# hackerling.net
KiCad netlist of a schematic drawn in EAGLE
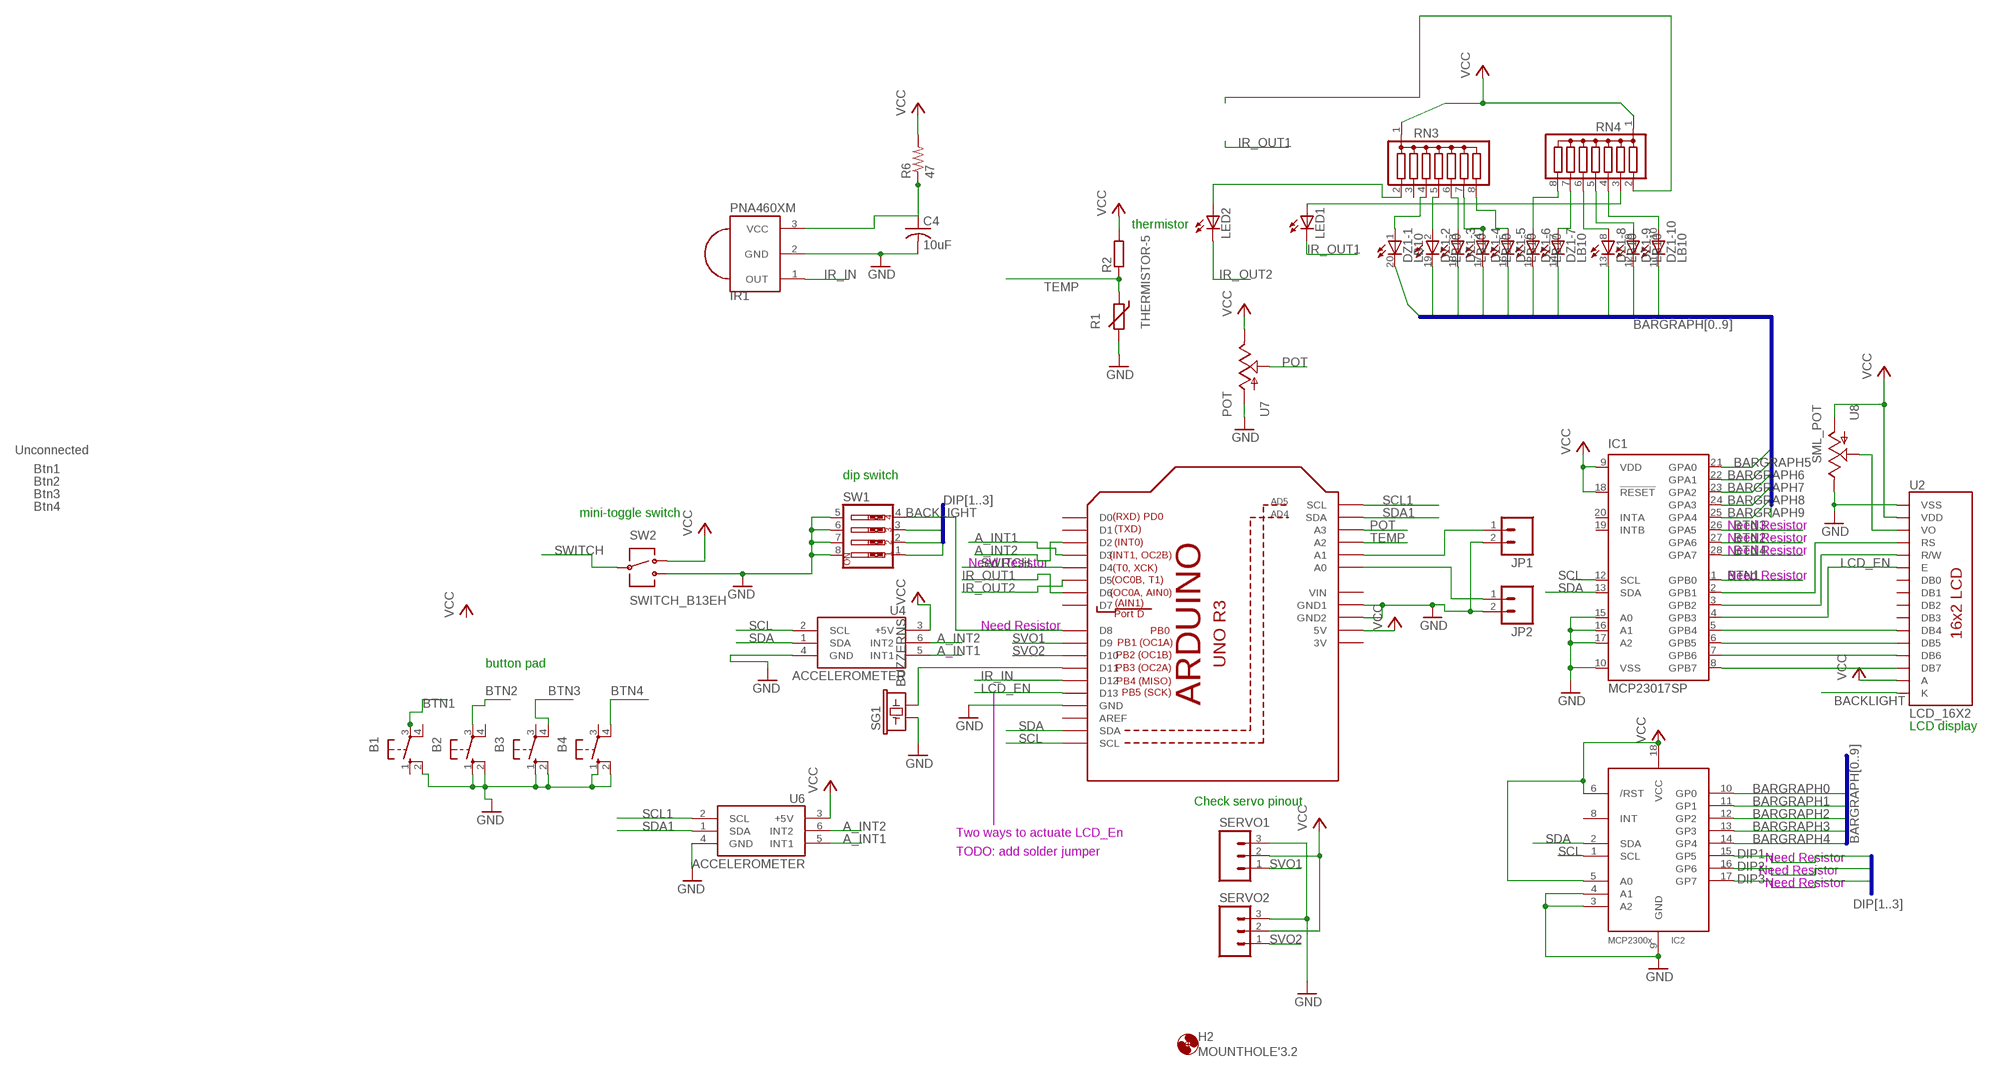
[diagram p0: schematic, sheet 1, part 1 of 2]
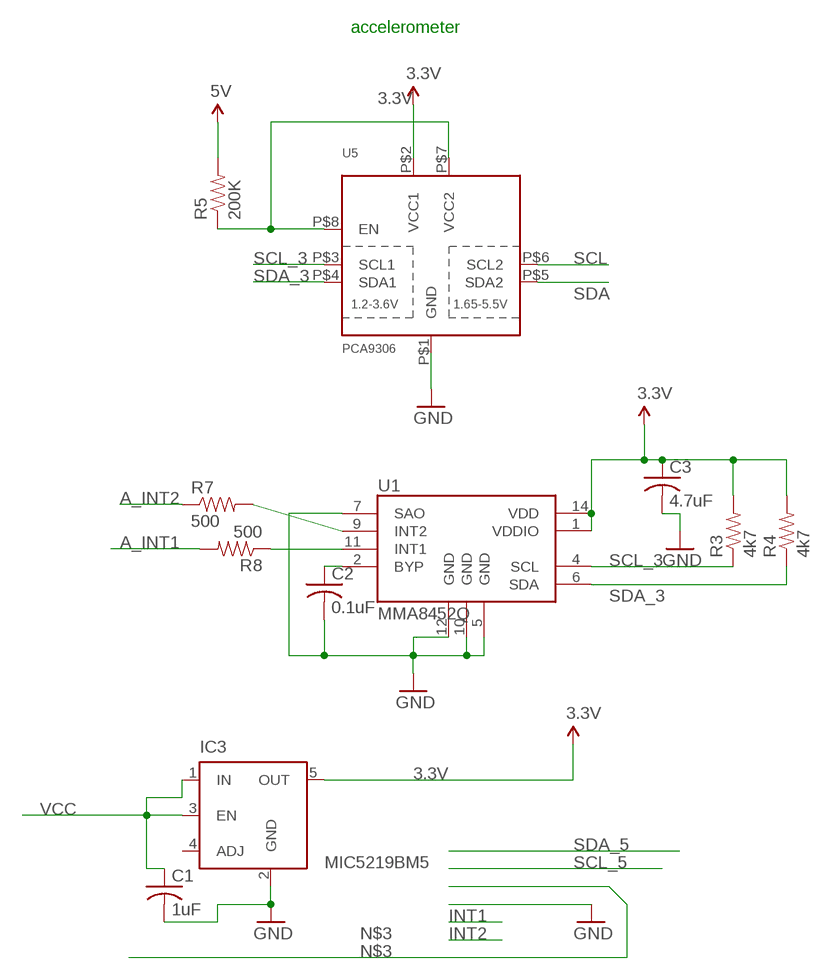
[diagram p1: schematic, sheet 1, part 2 of 2]

(export (version "E")
  (design (tool "Eeschema 10.0.6"))
  (components
    (comp (ref "B1")
      (value "SWITCH_BCF-4000")
      (footprint "eagle-import:SWITCH_B3F-4000")
      (libsource (lib "eagle-import") (part "SWITCH_BCF-4000"))
    )
    (comp (ref "B2")
      (value "SWITCH_BCF-4000")
      (footprint "eagle-import:SWITCH_B3F-4000")
      (libsource (lib "eagle-import") (part "SWITCH_BCF-4000"))
    )
    (comp (ref "B3")
      (value "SWITCH_BCF-4000")
      (footprint "eagle-import:SWITCH_B3F-4000")
      (libsource (lib "eagle-import") (part "SWITCH_BCF-4000"))
    )
    (comp (ref "B4")
      (value "SWITCH_BCF-4000")
      (footprint "eagle-import:SWITCH_B3F-4000")
      (libsource (lib "eagle-import") (part "SWITCH_BCF-4000"))
    )
    (comp (ref "C1")
      (value "1uF")
      (footprint "eagle-import:C0603K")
      (libsource (lib "eagle-import") (part "resistor_C-USC0603K"))
    )
    (comp (ref "C2")
      (value "0.1uF")
      (footprint "eagle-import:C0603K")
      (libsource (lib "eagle-import") (part "resistor_C-USC0603K"))
    )
    (comp (ref "C3")
      (value "4.7uF")
      (footprint "eagle-import:C0603K")
      (libsource (lib "eagle-import") (part "resistor_C-USC0603K"))
    )
    (comp (ref "C4")
      (value "10uF")
      (footprint "eagle-import:C050-050X075")
      (libsource (lib "eagle-import") (part "C-US050-050X075"))
    )
    (comp (ref "DZ1")
      (value "LB10")
      (footprint "eagle-import:LB10")
      (libsource (lib "eagle-import") (part "LB10"))
    )
    (comp (ref "H2")
      (value "MOUNTHOLE'3.2")
      (footprint "eagle-import:HOLE_3.2")
      (libsource (lib "eagle-import") (part "MOUNTHOLE'3.2"))
    )
    (comp (ref "IC1")
      (value "MCP23017SP")
      (footprint "eagle-import:DIL28-3")
      (libsource (lib "eagle-import") (part "MCP23017SP"))
    )
    (comp (ref "IC2")
      (value "MCP2300X/P")
      (footprint "eagle-import:DIL18")
      (libsource (lib "eagle-import") (part "MCP2300X/P"))
    )
    (comp (ref "IC3")
      (value "MIC5219BM5")
      (footprint "eagle-import:SOT23-5")
      (fields (field (name "MF") "ALTERA CORPORATION") (field (name "MPN") "MIC5219BM5 TR"))
      (libsource (lib "eagle-import") (part "MIC5219BM5"))
    )
    (comp (ref "IR1")
      (value "PNA460XM")
      (footprint "eagle-import:PNA460XM")
      (libsource (lib "eagle-import") (part "PNA460XM"))
    )
    (comp (ref "JP1")
      (value "M02LOCK")
      (footprint "eagle-import:1X02_LOCK")
      (libsource (lib "eagle-import") (part "M02LOCK"))
    )
    (comp (ref "JP2")
      (value "M02LOCK")
      (footprint "eagle-import:1X02_LOCK")
      (libsource (lib "eagle-import") (part "M02LOCK"))
    )
    (comp (ref "LED1")
      (value "LED5MM")
      (footprint "eagle-import:LED5MM")
      (libsource (lib "eagle-import") (part "LED5MM"))
    )
    (comp (ref "LED2")
      (value "LED5MM")
      (footprint "eagle-import:LED5MM")
      (libsource (lib "eagle-import") (part "LED5MM"))
    )
    (comp (ref "R1")
      (value "THERMISTOR-5")
      (footprint "eagle-import:R-5")
      (libsource (lib "eagle-import") (part "THERMISTOR-5"))
    )
    (comp (ref "R2")
      (value "R-EU_0204/7")
      (footprint "eagle-import:0204_7")
      (libsource (lib "eagle-import") (part "R-EU_0204/7"))
    )
    (comp (ref "R3")
      (value "4k7")
      (footprint "eagle-import:0603-RES")
      (libsource (lib "eagle-import") (part "RESISTOR0603-RES"))
    )
    (comp (ref "R4")
      (value "4k7")
      (footprint "eagle-import:0603-RES")
      (libsource (lib "eagle-import") (part "RESISTOR0603-RES"))
    )
    (comp (ref "R5")
      (value "200K")
      (footprint "eagle-import:0603-RES")
      (libsource (lib "eagle-import") (part "RESISTOR0603-RES"))
    )
    (comp (ref "R6")
      (value "47")
      (footprint "eagle-import:0204_7")
      (libsource (lib "eagle-import") (part "R-US_0204/7"))
    )
    (comp (ref "R7")
      (value "500")
      (footprint "eagle-import:0603-RES")
      (libsource (lib "eagle-import") (part "RESISTOR0603-RES"))
    )
    (comp (ref "R8")
      (value "500")
      (footprint "eagle-import:0603-RES")
      (libsource (lib "eagle-import") (part "RESISTOR0603-RES"))
    )
    (comp (ref "RN3")
      (value "G07R")
      (footprint "eagle-import:SIL8")
      (libsource (lib "eagle-import") (part "G07R"))
    )
    (comp (ref "RN4")
      (value "G07R")
      (footprint "eagle-import:SIL8")
      (libsource (lib "eagle-import") (part "G07R"))
    )
    (comp (ref "SERVO1")
      (value "M03LOCK")
      (footprint "eagle-import:1X03_LOCK")
      (libsource (lib "eagle-import") (part "M03LOCK"))
    )
    (comp (ref "SERVO2")
      (value "M03LOCK")
      (footprint "eagle-import:1X03_LOCK")
      (libsource (lib "eagle-import") (part "M03LOCK"))
    )
    (comp (ref "SG1")
      (value "BUZZERNS")
      (footprint "eagle-import:BUZZER-12MM-NS")
      (libsource (lib "eagle-import") (part "BUZZERNS"))
    )
    (comp (ref "SW1")
      (value "SW_DIP-4")
      (footprint "eagle-import:EDG-04")
      (libsource (lib "eagle-import") (part "SW_DIP-4"))
    )
    (comp (ref "SW2")
      (value "SWITCH_B13EH")
      (footprint "eagle-import:SWITCH_B13EH")
      (libsource (lib "eagle-import") (part "SWITCH_B13EH"))
    )
    (comp (ref "U1")
      (value "MMA8452Q")
      (footprint "eagle-import:QFN-16(5X3)")
      (libsource (lib "eagle-import") (part "MMA8452Q"))
    )
    (comp (ref "U2")
      (value "LCD_16X2")
      (footprint "eagle-import:LCD_16X2")
      (libsource (lib "eagle-import") (part "LCD_16X2"))
    )
    (comp (ref "U3")
      (value "ARDUINOR3-BPLACE")
      (footprint "eagle-import:ARDUINOR3-BPLACE")
      (libsource (lib "eagle-import") (part "ARDUINOR3-BPLACE"))
    )
    (comp (ref "U4")
      (value "ACCELEROMETER")
      (footprint "eagle-import:ACCELEROMETER")
      (libsource (lib "eagle-import") (part "ACCELEROMETER"))
    )
    (comp (ref "U5")
      (value "PCA9306")
      (footprint "eagle-import:VSSOP-8")
      (libsource (lib "eagle-import") (part "PCA9306"))
    )
    (comp (ref "U6")
      (value "ACCELEROMETER")
      (footprint "eagle-import:ACCELEROMETER")
      (libsource (lib "eagle-import") (part "ACCELEROMETER"))
    )
    (comp (ref "U7")
      (value "POT")
      (footprint "eagle-import:ALS_POT")
      (libsource (lib "eagle-import") (part "POT"))
    )
    (comp (ref "U8")
      (value "SML_POT")
      (footprint "eagle-import:SML_POT")
      (libsource (lib "eagle-import") (part "SML_POT"))
    )
  )
  (nets
    (net (code "1") (name "/3V") (class "Default")
      (node (ref "U3") (pin "3V") (pinfunction "3V_3V") (pintype "power_in"))
    )
    (net (code "2") (name "/A_INT1") (class "Default")
      (node (ref "R8") (pin "2") (pinfunction "2_2") (pintype "passive"))
      (node (ref "U3") (pin "D3") (pinfunction "D3_D3") (pintype "bidirectional"))
      (node (ref "U4") (pin "5") (pinfunction "INT1_5") (pintype "bidirectional"))
      (node (ref "U6") (pin "5") (pinfunction "INT1_5") (pintype "bidirectional"))
    )
    (net (code "3") (name "/A_INT2") (class "Default")
      (node (ref "R7") (pin "1") (pinfunction "1_1") (pintype "passive"))
      (node (ref "U3") (pin "D2") (pinfunction "D2_D2") (pintype "bidirectional"))
      (node (ref "U4") (pin "6") (pinfunction "INT2_6") (pintype "bidirectional"))
      (node (ref "U6") (pin "6") (pinfunction "INT2_6") (pintype "bidirectional"))
    )
    (net (code "4") (name "/BACKLIGHT") (class "Default")
      (node (ref "SW1") (pin "4") (pinfunction "4_4") (pintype "passive"))
      (node (ref "U2") (pin "16") (pinfunction "K_16") (pintype "power_in"))
      (node (ref "U3") (pin "D8") (pinfunction "D8_D8") (pintype "bidirectional"))
    )
    (net (code "5") (name "/BARGRAPH0") (class "Default")
      (node (ref "DZ1") (pin "20") (pinfunction "C_20") (pintype "passive"))
      (node (ref "IC2") (pin "10") (pinfunction "GP0_10") (pintype "bidirectional"))
    )
    (net (code "6") (name "/BARGRAPH1") (class "Default")
      (node (ref "DZ1") (pin "19") (pinfunction "C_19") (pintype "passive"))
      (node (ref "IC2") (pin "11") (pinfunction "GP1_11") (pintype "bidirectional"))
    )
    (net (code "7") (name "/BARGRAPH2") (class "Default")
      (node (ref "DZ1") (pin "18") (pinfunction "C_18") (pintype "passive"))
      (node (ref "IC2") (pin "12") (pinfunction "GP2_12") (pintype "bidirectional"))
    )
    (net (code "8") (name "/BARGRAPH3") (class "Default")
      (node (ref "DZ1") (pin "17") (pinfunction "C_17") (pintype "passive"))
      (node (ref "IC2") (pin "13") (pinfunction "GP3_13") (pintype "bidirectional"))
    )
    (net (code "9") (name "/BARGRAPH4") (class "Default")
      (node (ref "DZ1") (pin "16") (pinfunction "C_16") (pintype "passive"))
      (node (ref "IC2") (pin "14") (pinfunction "GP4_14") (pintype "bidirectional"))
    )
    (net (code "10") (name "/BARGRAPH5") (class "Default")
      (node (ref "DZ1") (pin "15") (pinfunction "C_15") (pintype "passive"))
      (node (ref "IC1") (pin "21") (pinfunction "GPA0_21") (pintype "bidirectional"))
    )
    (net (code "11") (name "/BARGRAPH6") (class "Default")
      (node (ref "DZ1") (pin "14") (pinfunction "C_14") (pintype "passive"))
      (node (ref "IC1") (pin "22") (pinfunction "GPA1_22") (pintype "bidirectional"))
    )
    (net (code "12") (name "/BARGRAPH7") (class "Default")
      (node (ref "DZ1") (pin "13") (pinfunction "C_13") (pintype "passive"))
      (node (ref "IC1") (pin "23") (pinfunction "GPA2_23") (pintype "bidirectional"))
    )
    (net (code "13") (name "/BARGRAPH8") (class "Default")
      (node (ref "DZ1") (pin "12") (pinfunction "C_12") (pintype "passive"))
      (node (ref "IC1") (pin "24") (pinfunction "GPA3_24") (pintype "bidirectional"))
    )
    (net (code "14") (name "/BARGRAPH9") (class "Default")
      (node (ref "DZ1") (pin "11") (pinfunction "C_11") (pintype "passive"))
      (node (ref "IC1") (pin "25") (pinfunction "GPA4_25") (pintype "bidirectional"))
    )
    (net (code "16") (name "/BTN1") (class "Default")
      (node (ref "B1") (pin "3") (pinfunction "P_3") (pintype "passive"))
      (node (ref "IC1") (pin "1") (pinfunction "GPB0_1") (pintype "bidirectional"))
    )
    (net (code "17") (name "/BTN2") (class "Default")
      (node (ref "B2") (pin "3") (pinfunction "P_3") (pintype "passive"))
      (node (ref "IC1") (pin "27") (pinfunction "GPA6_27") (pintype "bidirectional"))
    )
    (net (code "18") (name "/BTN3") (class "Default")
      (node (ref "B3") (pin "4") (pinfunction "P1_4") (pintype "passive"))
      (node (ref "IC1") (pin "26") (pinfunction "GPA5_26") (pintype "bidirectional"))
    )
    (net (code "19") (name "/BTN4") (class "Default")
      (node (ref "B4") (pin "4") (pinfunction "P1_4") (pintype "passive"))
      (node (ref "IC1") (pin "28") (pinfunction "GPA7_28") (pintype "bidirectional"))
    )
    (net (code "20") (name "/DIP1") (class "Default")
      (node (ref "IC2") (pin "15") (pinfunction "GP5_15") (pintype "bidirectional"))
      (node (ref "SW1") (pin "1") (pinfunction "1_1") (pintype "passive"))
    )
    (net (code "21") (name "/DIP2") (class "Default")
      (node (ref "IC2") (pin "16") (pinfunction "GP6_16") (pintype "bidirectional"))
      (node (ref "SW1") (pin "2") (pinfunction "2_2") (pintype "passive"))
    )
    (net (code "22") (name "/DIP3") (class "Default")
      (node (ref "IC2") (pin "17") (pinfunction "GP7_17") (pintype "bidirectional"))
      (node (ref "SW1") (pin "3") (pinfunction "3_3") (pintype "passive"))
    )
    (net (code "26") (name "/IR_IN") (class "Default")
      (node (ref "IR1") (pin "1") (pinfunction "OUT_1") (pintype "output"))
      (node (ref "U3") (pin "D12") (pinfunction "D12_D12") (pintype "bidirectional"))
    )
    (net (code "27") (name "/IR_OUT1") (class "Default")
      (node (ref "LED1") (pin "K") (pinfunction "C_K") (pintype "passive"))
      (node (ref "U3") (pin "D6") (pinfunction "D6_D6") (pintype "bidirectional"))
    )
    (net (code "28") (name "/IR_OUT2") (class "Default")
      (node (ref "LED2") (pin "K") (pinfunction "C_K") (pintype "passive"))
      (node (ref "U3") (pin "D5") (pinfunction "D5_D5") (pintype "bidirectional"))
    )
    (net (code "29") (name "/LCD_EN") (class "Default")
      (node (ref "IC1") (pin "4") (pinfunction "GPB3_4") (pintype "bidirectional"))
      (node (ref "U2") (pin "6") (pinfunction "E_6") (pintype "input"))
      (node (ref "U3") (pin "D13") (pinfunction "D13_D13") (pintype "bidirectional"))
    )
    (net (code "30") (name "/N$3") (class "Default")
      (node (ref "IC1") (pin "6") (pinfunction "GPB5_6") (pintype "bidirectional"))
      (node (ref "U2") (pin "12") (pinfunction "DB5_12") (pintype "bidirectional"))
      (node (ref "U2") (pin "B12") (pinfunction "DB5_B12") (pintype "bidirectional"))
    )
    (net (code "31") (name "/POT") (class "Default")
      (node (ref "U3") (pin "A3") (pinfunction "A3_A3") (pintype "bidirectional"))
      (node (ref "U7") (pin "P$2") (pinfunction "S_P$2") (pintype "passive"))
    )
    (net (code "32") (name "/SCL") (class "Default")
      (node (ref "IC1") (pin "12") (pinfunction "SCL_12") (pintype "input"))
      (node (ref "IC2") (pin "1") (pinfunction "SCL_1") (pintype "bidirectional"))
      (node (ref "U3") (pin "SCL") (pinfunction "SCL_SCL") (pintype "bidirectional"))
      (node (ref "U4") (pin "2") (pinfunction "SCL_2") (pintype "bidirectional"))
      (node (ref "U5") (pin "P$6") (pinfunction "SCL2_P$6") (pintype "bidirectional"))
    )
    (net (code "33") (name "/SCL1") (class "Default")
      (node (ref "U3") (pin "A5") (pinfunction "SCL_A5") (pintype "bidirectional"))
      (node (ref "U6") (pin "2") (pinfunction "SCL_2") (pintype "bidirectional"))
    )
    (net (code "34") (name "/SCL_3") (class "Default")
      (node (ref "R3") (pin "1") (pinfunction "1_1") (pintype "passive"))
      (node (ref "U1") (pin "4") (pinfunction "SCL_4") (pintype "bidirectional"))
      (node (ref "U5") (pin "P$3") (pinfunction "SCL1_P$3") (pintype "bidirectional"))
    )
    (net (code "36") (name "/SDA") (class "Default")
      (node (ref "IC1") (pin "13") (pinfunction "SDA_13") (pintype "bidirectional"))
      (node (ref "IC2") (pin "2") (pinfunction "SDA_2") (pintype "bidirectional"))
      (node (ref "U3") (pin "SDA") (pinfunction "SDA_SDA") (pintype "bidirectional"))
      (node (ref "U4") (pin "1") (pinfunction "SDA_1") (pintype "bidirectional"))
      (node (ref "U5") (pin "P$5") (pinfunction "SDA2_P$5") (pintype "bidirectional"))
    )
    (net (code "37") (name "/SDA1") (class "Default")
      (node (ref "U3") (pin "A4") (pinfunction "SDA_A4") (pintype "bidirectional"))
      (node (ref "U6") (pin "1") (pinfunction "SDA_1") (pintype "bidirectional"))
    )
    (net (code "38") (name "/SDA_3") (class "Default")
      (node (ref "R4") (pin "1") (pinfunction "1_1") (pintype "passive"))
      (node (ref "U1") (pin "6") (pinfunction "SDA_6") (pintype "bidirectional"))
      (node (ref "U5") (pin "P$4") (pinfunction "SDA1_P$4") (pintype "bidirectional"))
    )
    (net (code "40") (name "/SVO1") (class "Default")
      (node (ref "SERVO1") (pin "1") (pinfunction "1_1") (pintype "passive"))
      (node (ref "U3") (pin "D9") (pinfunction "D9_D9") (pintype "bidirectional"))
    )
    (net (code "41") (name "/SVO2") (class "Default")
      (node (ref "SERVO2") (pin "1") (pinfunction "1_1") (pintype "passive"))
      (node (ref "U3") (pin "D10") (pinfunction "D10_D10") (pintype "bidirectional"))
    )
    (net (code "42") (name "/SWITCH") (class "Default")
      (node (ref "SW2") (pin "2") (pinfunction "2_2") (pintype "bidirectional"))
      (node (ref "U3") (pin "D4") (pinfunction "D4_D4") (pintype "bidirectional"))
    )
    (net (code "43") (name "/TEMP") (class "Default")
      (node (ref "R1") (pin "1") (pinfunction "1_1") (pintype "passive"))
      (node (ref "R2") (pin "1") (pinfunction "1_1") (pintype "passive"))
      (node (ref "U3") (pin "A2") (pinfunction "A2_A2") (pintype "bidirectional"))
    )
    (net (code "44") (name "/VIN") (class "Default")
      (node (ref "U3") (pin "VIN") (pinfunction "VIN_VIN") (pintype "power_in"))
    )
    (net (code "45") (name "3.3V") (class "Default")
      (node (ref "C3") (pin "1") (pinfunction "1_1") (pintype "passive"))
      (node (ref "IC3") (pin "5") (pinfunction "OUT_5") (pintype "output"))
      (node (ref "R3") (pin "2") (pinfunction "2_2") (pintype "passive"))
      (node (ref "R4") (pin "2") (pinfunction "2_2") (pintype "passive"))
      (node (ref "U1") (pin "1") (pinfunction "VDDIO_1") (pintype "bidirectional"))
      (node (ref "U1") (pin "14") (pinfunction "VDD_14") (pintype "bidirectional"))
      (node (ref "U5") (pin "P$2") (pinfunction "VCC1_P$2") (pintype "bidirectional"))
    )
    (net (code "46") (name "5V") (class "Default")
      (node (ref "C1") (pin "1") (pinfunction "1_1") (pintype "passive"))
      (node (ref "IC1") (pin "18") (pinfunction "~{RESET}_18") (pintype "input"))
      (node (ref "IC1") (pin "9") (pinfunction "VDD_9") (pintype "power_in"))
      (node (ref "IC2") (pin "18") (pinfunction "VCC_18") (pintype "power_in"))
      (node (ref "IC2") (pin "5") (pinfunction "A0_5") (pintype "input"))
      (node (ref "IC2") (pin "6") (pinfunction "/RST_6") (pintype "input"))
      (node (ref "IC3") (pin "1") (pinfunction "IN_1") (pintype "input"))
      (node (ref "IC3") (pin "3") (pinfunction "EN_3") (pintype "input"))
      (node (ref "R2") (pin "2") (pinfunction "2_2") (pintype "passive"))
      (node (ref "R5") (pin "2") (pinfunction "2_2") (pintype "passive"))
      (node (ref "R6") (pin "2") (pinfunction "2_2") (pintype "passive"))
      (node (ref "RN3") (pin "1") (pinfunction "1_1") (pintype "passive"))
      (node (ref "RN4") (pin "1") (pinfunction "1_1") (pintype "passive"))
      (node (ref "SERVO1") (pin "2") (pinfunction "2_2") (pintype "passive"))
      (node (ref "SERVO2") (pin "2") (pinfunction "2_2") (pintype "passive"))
      (node (ref "SW2") (pin "1") (pinfunction "1_1") (pintype "bidirectional"))
      (node (ref "U2") (pin "15") (pinfunction "A_15") (pintype "power_in"))
      (node (ref "U2") (pin "2") (pinfunction "VDD_2") (pintype "power_in"))
      (node (ref "U2") (pin "B2") (pinfunction "VDD_B2") (pintype "power_in"))
      (node (ref "U3") (pin "5V") (pinfunction "5V_5V") (pintype "power_in"))
      (node (ref "U4") (pin "3") (pinfunction "+5V_3") (pintype "bidirectional"))
      (node (ref "U6") (pin "3") (pinfunction "+5V_3") (pintype "bidirectional"))
      (node (ref "U7") (pin "P$3") (pinfunction "E_P$3") (pintype "passive"))
      (node (ref "U8") (pin "A") (pinfunction "A_A") (pintype "passive"))
    )
    (net (code "47") (name "GND") (class "Default")
      (node (ref "B1") (pin "2") (pinfunction "S1_2") (pintype "passive"))
      (node (ref "B2") (pin "1") (pinfunction "S_1") (pintype "passive"))
      (node (ref "B2") (pin "2") (pinfunction "S1_2") (pintype "passive"))
      (node (ref "B3") (pin "1") (pinfunction "S_1") (pintype "passive"))
      (node (ref "B3") (pin "2") (pinfunction "S1_2") (pintype "passive"))
      (node (ref "B4") (pin "1") (pinfunction "S_1") (pintype "passive"))
      (node (ref "B4") (pin "2") (pinfunction "S1_2") (pintype "passive"))
      (node (ref "C1") (pin "2") (pinfunction "2_2") (pintype "passive"))
      (node (ref "C2") (pin "2") (pinfunction "2_2") (pintype "passive"))
      (node (ref "C3") (pin "2") (pinfunction "2_2") (pintype "passive"))
      (node (ref "C4") (pin "2") (pinfunction "2_2") (pintype "passive"))
      (node (ref "IC1") (pin "10") (pinfunction "VSS_10") (pintype "power_in"))
      (node (ref "IC1") (pin "15") (pinfunction "A0_15") (pintype "input"))
      (node (ref "IC1") (pin "16") (pinfunction "A1_16") (pintype "input"))
      (node (ref "IC1") (pin "17") (pinfunction "A2_17") (pintype "input"))
      (node (ref "IC2") (pin "3") (pinfunction "A2_3") (pintype "input"))
      (node (ref "IC2") (pin "4") (pinfunction "A1_4") (pintype "input"))
      (node (ref "IC2") (pin "9") (pinfunction "GND_9") (pintype "power_in"))
      (node (ref "IC3") (pin "2") (pinfunction "GND_2") (pintype "power_in"))
      (node (ref "IR1") (pin "2") (pinfunction "GND_2") (pintype "power_in"))
      (node (ref "JP1") (pin "2") (pinfunction "2_2") (pintype "passive"))
      (node (ref "JP2") (pin "2") (pinfunction "2_2") (pintype "passive"))
      (node (ref "R1") (pin "2") (pinfunction "2_2") (pintype "passive"))
      (node (ref "SERVO1") (pin "3") (pinfunction "3_3") (pintype "passive"))
      (node (ref "SERVO2") (pin "3") (pinfunction "3_3") (pintype "passive"))
      (node (ref "SG1") (pin "+") (pinfunction "1_+") (pintype "passive"))
      (node (ref "SW1") (pin "5") (pinfunction "5_5") (pintype "passive"))
      (node (ref "SW1") (pin "6") (pinfunction "6_6") (pintype "passive"))
      (node (ref "SW1") (pin "7") (pinfunction "7_7") (pintype "passive"))
      (node (ref "SW1") (pin "8") (pinfunction "8_8") (pintype "passive"))
      (node (ref "SW2") (pin "3") (pinfunction "3_3") (pintype "bidirectional"))
      (node (ref "U1") (pin "10") (pinfunction "GND_10") (pintype "bidirectional"))
      (node (ref "U1") (pin "12") (pinfunction "GND_12") (pintype "bidirectional"))
      (node (ref "U1") (pin "5") (pinfunction "GND_5") (pintype "bidirectional"))
      (node (ref "U1") (pin "7") (pinfunction "SAO_7") (pintype "bidirectional"))
      (node (ref "U2") (pin "1") (pinfunction "VSS_1") (pintype "power_in"))
      (node (ref "U2") (pin "B1") (pinfunction "VSS_B1") (pintype "power_in"))
      (node (ref "U3") (pin "GND") (pinfunction "GND_GND") (pintype "power_in"))
      (node (ref "U3") (pin "GND1") (pinfunction "GND1_GND1") (pintype "power_in"))
      (node (ref "U3") (pin "GND2") (pinfunction "GND2_GND2") (pintype "power_in"))
      (node (ref "U4") (pin "4") (pinfunction "GND_4") (pintype "bidirectional"))
      (node (ref "U5") (pin "P$1") (pinfunction "GND_P$1") (pintype "bidirectional"))
      (node (ref "U6") (pin "4") (pinfunction "GND_4") (pintype "bidirectional"))
      (node (ref "U7") (pin "P$1") (pinfunction "A_P$1") (pintype "passive"))
      (node (ref "U8") (pin "E") (pinfunction "E_E") (pintype "passive"))
    )
    (net (code "48") (name "Net-(DZ1A-A)") (class "Default")
      (node (ref "DZ1") (pin "1") (pinfunction "A_1") (pintype "passive"))
      (node (ref "RN3") (pin "4") (pinfunction "4_4") (pintype "passive"))
    )
    (net (code "49") (name "Net-(DZ1B-A)") (class "Default")
      (node (ref "DZ1") (pin "10") (pinfunction "A_10") (pintype "passive"))
      (node (ref "RN4") (pin "4") (pinfunction "4_4") (pintype "passive"))
    )
    (net (code "50") (name "Net-(DZ1C-A)") (class "Default")
      (node (ref "DZ1") (pin "2") (pinfunction "A_2") (pintype "passive"))
      (node (ref "RN3") (pin "5") (pinfunction "5_5") (pintype "passive"))
    )
    (net (code "51") (name "Net-(DZ1D-A)") (class "Default")
      (node (ref "DZ1") (pin "3") (pinfunction "A_3") (pintype "passive"))
      (node (ref "RN3") (pin "6") (pinfunction "6_6") (pintype "passive"))
    )
    (net (code "52") (name "Net-(DZ1E-A)") (class "Default")
      (node (ref "DZ1") (pin "4") (pinfunction "A_4") (pintype "passive"))
      (node (ref "RN3") (pin "7") (pinfunction "7_7") (pintype "passive"))
    )
    (net (code "53") (name "Net-(DZ1F-A)") (class "Default")
      (node (ref "DZ1") (pin "5") (pinfunction "A_5") (pintype "passive"))
      (node (ref "RN3") (pin "8") (pinfunction "8_8") (pintype "passive"))
    )
    (net (code "54") (name "Net-(DZ1G-A)") (class "Default")
      (node (ref "DZ1") (pin "6") (pinfunction "A_6") (pintype "passive"))
      (node (ref "RN4") (pin "8") (pinfunction "8_8") (pintype "passive"))
    )
    (net (code "55") (name "Net-(DZ1H-A)") (class "Default")
      (node (ref "DZ1") (pin "7") (pinfunction "A_7") (pintype "passive"))
      (node (ref "RN4") (pin "7") (pinfunction "7_7") (pintype "passive"))
    )
    (net (code "56") (name "Net-(DZ1I-A)") (class "Default")
      (node (ref "DZ1") (pin "8") (pinfunction "A_8") (pintype "passive"))
      (node (ref "RN4") (pin "6") (pinfunction "6_6") (pintype "passive"))
    )
    (net (code "57") (name "Net-(DZ1J-A)") (class "Default")
      (node (ref "DZ1") (pin "9") (pinfunction "A_9") (pintype "passive"))
      (node (ref "RN4") (pin "5") (pinfunction "5_5") (pintype "passive"))
    )
    (net (code "58") (name "Net-(IC1-GPB1)") (class "Default")
      (node (ref "IC1") (pin "2") (pinfunction "GPB1_2") (pintype "bidirectional"))
      (node (ref "U2") (pin "4") (pinfunction "RS_4") (pintype "input"))
    )
    (net (code "59") (name "Net-(IC1-GPB2)") (class "Default")
      (node (ref "IC1") (pin "3") (pinfunction "GPB2_3") (pintype "bidirectional"))
      (node (ref "U2") (pin "5") (pinfunction "R/W_5") (pintype "input"))
    )
    (net (code "60") (name "Net-(IC1-GPB4)") (class "Default")
      (node (ref "IC1") (pin "5") (pinfunction "GPB4_5") (pintype "bidirectional"))
      (node (ref "U2") (pin "11") (pinfunction "DB4_11") (pintype "bidirectional"))
    )
    (net (code "61") (name "Net-(IC1-GPB6)") (class "Default")
      (node (ref "IC1") (pin "7") (pinfunction "GPB6_7") (pintype "bidirectional"))
      (node (ref "U2") (pin "13") (pinfunction "DB6_13") (pintype "bidirectional"))
      (node (ref "U2") (pin "B13") (pinfunction "DB6_B13") (pintype "bidirectional"))
    )
    (net (code "62") (name "Net-(IC1-GPB7)") (class "Default")
      (node (ref "IC1") (pin "8") (pinfunction "GPB7_8") (pintype "bidirectional"))
      (node (ref "U2") (pin "14") (pinfunction "DB7_14") (pintype "bidirectional"))
    )
    (net (code "63") (name "Net-(IR1-VCC)") (class "Default")
      (node (ref "C4") (pin "1") (pinfunction "1_1") (pintype "passive"))
      (node (ref "IR1") (pin "3") (pinfunction "VCC_3") (pintype "power_in"))
      (node (ref "R6") (pin "1") (pinfunction "1_1") (pintype "passive"))
    )
    (net (code "64") (name "Net-(JP1-Pad1)") (class "Default")
      (node (ref "JP1") (pin "1") (pinfunction "1_1") (pintype "passive"))
      (node (ref "U3") (pin "A1") (pinfunction "A1_A1") (pintype "bidirectional"))
    )
    (net (code "65") (name "Net-(JP2-Pad1)") (class "Default")
      (node (ref "JP2") (pin "1") (pinfunction "1_1") (pintype "passive"))
      (node (ref "U3") (pin "A0") (pinfunction "A0_A0") (pintype "bidirectional"))
    )
    (net (code "66") (name "Net-(LED1-PadA)") (class "Default")
      (node (ref "LED1") (pin "A") (pinfunction "A_A") (pintype "passive"))
      (node (ref "RN4") (pin "3") (pinfunction "3_3") (pintype "passive"))
    )
    (net (code "67") (name "Net-(LED2-PadA)") (class "Default")
      (node (ref "LED2") (pin "A") (pinfunction "A_A") (pintype "passive"))
      (node (ref "RN3") (pin "2") (pinfunction "2_2") (pintype "passive"))
    )
    (net (code "68") (name "Net-(SG1-2)") (class "Default")
      (node (ref "SG1") (pin "-") (pinfunction "2_-") (pintype "passive"))
      (node (ref "U3") (pin "D11") (pinfunction "D11_D11") (pintype "bidirectional"))
    )
    (net (code "69") (name "Net-(U1-BYP)") (class "Default")
      (node (ref "C2") (pin "1") (pinfunction "1_1") (pintype "passive"))
      (node (ref "U1") (pin "2") (pinfunction "BYP_2") (pintype "bidirectional"))
    )
    (net (code "70") (name "Net-(U1-INT1)") (class "Default")
      (node (ref "R8") (pin "1") (pinfunction "1_1") (pintype "passive"))
      (node (ref "U1") (pin "11") (pinfunction "INT1_11") (pintype "bidirectional"))
    )
    (net (code "71") (name "Net-(U1-INT2)") (class "Default")
      (node (ref "R7") (pin "2") (pinfunction "2_2") (pintype "passive"))
      (node (ref "U1") (pin "9") (pinfunction "INT2_9") (pintype "bidirectional"))
    )
    (net (code "72") (name "Net-(U2-VO)") (class "Default")
      (node (ref "U2") (pin "3") (pinfunction "VO_3") (pintype "bidirectional"))
      (node (ref "U8") (pin "S") (pinfunction "S_S") (pintype "passive"))
    )
    (net (code "73") (name "Net-(U5-EN)") (class "Default")
      (node (ref "R5") (pin "1") (pinfunction "1_1") (pintype "passive"))
      (node (ref "U5") (pin "P$7") (pinfunction "VCC2_P$7") (pintype "bidirectional"))
      (node (ref "U5") (pin "P$8") (pinfunction "EN_P$8") (pintype "bidirectional"))
    )
    (net (code "74") (name "unconnected-(B1-P1-Pad4)") (class "Default")
      (node (ref "B1") (pin "4") (pinfunction "P1_4") (pintype "passive"))
    )
    (net (code "75") (name "unconnected-(B1-S-Pad1)") (class "Default")
      (node (ref "B1") (pin "1") (pinfunction "S_1") (pintype "passive"))
    )
    (net (code "76") (name "unconnected-(B2-P1-Pad4)") (class "Default")
      (node (ref "B2") (pin "4") (pinfunction "P1_4") (pintype "passive"))
    )
    (net (code "77") (name "unconnected-(B3-P-Pad3)") (class "Default")
      (node (ref "B3") (pin "3") (pinfunction "P_3") (pintype "passive"))
    )
    (net (code "78") (name "unconnected-(B4-P-Pad3)") (class "Default")
      (node (ref "B4") (pin "3") (pinfunction "P_3") (pintype "passive"))
    )
    (net (code "79") (name "unconnected-(IC1-INTA-Pad20)") (class "Default")
      (node (ref "IC1") (pin "20") (pinfunction "INTA_20") (pintype "output"))
    )
    (net (code "80") (name "unconnected-(IC1-INTB-Pad19)") (class "Default")
      (node (ref "IC1") (pin "19") (pinfunction "INTB_19") (pintype "output"))
    )
    (net (code "81") (name "unconnected-(IC2-INT-Pad8)") (class "Default")
      (node (ref "IC2") (pin "8") (pinfunction "INT_8") (pintype "output"))
    )
    (net (code "82") (name "unconnected-(IC3-ADJ-Pad4)") (class "Default")
      (node (ref "IC3") (pin "4") (pinfunction "ADJ_4") (pintype "passive"))
    )
    (net (code "83") (name "unconnected-(RN3-Pad3)") (class "Default")
      (node (ref "RN3") (pin "3") (pinfunction "3_3") (pintype "passive"))
    )
    (net (code "84") (name "unconnected-(RN4-Pad2)") (class "Default")
      (node (ref "RN4") (pin "2") (pinfunction "2_2") (pintype "passive"))
    )
    (net (code "85") (name "unconnected-(U2-DB0-Pad7)") (class "Default")
      (node (ref "U2") (pin "7") (pinfunction "DB0_7") (pintype "bidirectional"))
    )
    (net (code "86") (name "unconnected-(U2-DB1-Pad8)") (class "Default")
      (node (ref "U2") (pin "8") (pinfunction "DB1_8") (pintype "bidirectional"))
    )
    (net (code "87") (name "unconnected-(U2-DB2-Pad9)") (class "Default")
      (node (ref "U2") (pin "9") (pinfunction "DB2_9") (pintype "bidirectional"))
    )
    (net (code "88") (name "unconnected-(U2-DB3-Pad10)") (class "Default")
      (node (ref "U2") (pin "10") (pinfunction "DB3_10") (pintype "bidirectional"))
    )
    (net (code "89") (name "unconnected-(U3-PadAREF)") (class "Default")
      (node (ref "U3") (pin "AREF") (pinfunction "AREF_AREF") (pintype "bidirectional"))
    )
    (net (code "90") (name "unconnected-(U3-PadD0)") (class "Default")
      (node (ref "U3") (pin "D0") (pinfunction "D0_D0") (pintype "bidirectional"))
    )
    (net (code "91") (name "unconnected-(U3-PadD1)") (class "Default")
      (node (ref "U3") (pin "D1") (pinfunction "D1_D1") (pintype "bidirectional"))
    )
    (net (code "92") (name "unconnected-(U3-PadD7)") (class "Default")
      (node (ref "U3") (pin "D7") (pinfunction "D7_D7") (pintype "bidirectional"))
    )
  )
)
